# GBCZ.net
KiCad netlist of a schematic drawn in EAGLE
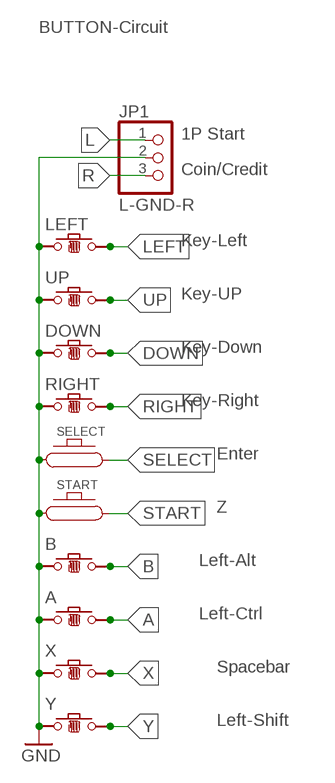
[diagram p0: schematic, sheet 1]

(export (version "E")
  (design (tool "Eeschema 10.0.6"))
  (components
    (comp (ref "A")
      (value "GBC_BTN")
      (footprint "eagle-import:GBC_BTN")
      (libsource (lib "eagle-import") (part "GBC_BTN"))
    )
    (comp (ref "B")
      (value "GBC_BTN")
      (footprint "eagle-import:GBC_BTN")
      (libsource (lib "eagle-import") (part "GBC_BTN"))
    )
    (comp (ref "DOWN")
      (value "GBC_BTN")
      (footprint "eagle-import:GBC_BTN")
      (libsource (lib "eagle-import") (part "GBC_BTN"))
    )
    (comp (ref "JP1")
      (value "L-GND-R")
      (footprint "eagle-import:1X03")
      (libsource (lib "eagle-import") (part "PINHD-1X3"))
    )
    (comp (ref "LEFT")
      (value "GBC_BTN")
      (footprint "eagle-import:GBC_BTN")
      (libsource (lib "eagle-import") (part "GBC_BTN"))
    )
    (comp (ref "RIGHT")
      (value "GBC_BTN")
      (footprint "eagle-import:GBC_BTN")
      (libsource (lib "eagle-import") (part "GBC_BTN"))
    )
    (comp (ref "SELECT")
      (value "GBC_BTN_START")
      (footprint "eagle-import:GBC_BTN_START")
      (libsource (lib "eagle-import") (part "GBC_BTN_START"))
    )
    (comp (ref "START")
      (value "GBC_BTN_START")
      (footprint "eagle-import:GBC_BTN_START")
      (libsource (lib "eagle-import") (part "GBC_BTN_START"))
    )
    (comp (ref "UP")
      (value "GBC_BTN")
      (footprint "eagle-import:GBC_BTN")
      (libsource (lib "eagle-import") (part "GBC_BTN"))
    )
    (comp (ref "X")
      (value "GBC_BTN")
      (footprint "eagle-import:GBC_BTN")
      (libsource (lib "eagle-import") (part "GBC_BTN"))
    )
    (comp (ref "Y")
      (value "GBC_BTN")
      (footprint "eagle-import:GBC_BTN")
      (libsource (lib "eagle-import") (part "GBC_BTN"))
    )
  )
  (nets
    (net (code "1") (name "A") (class "Default")
      (node (ref "A") (pin "P$2") (pinfunction "P$2_P$2") (pintype "passive"))
    )
    (net (code "2") (name "B") (class "Default")
      (node (ref "B") (pin "P$2") (pinfunction "P$2_P$2") (pintype "passive"))
    )
    (net (code "3") (name "DOWN") (class "Default")
      (node (ref "DOWN") (pin "P$2") (pinfunction "P$2_P$2") (pintype "passive"))
    )
    (net (code "4") (name "GND") (class "Default")
      (node (ref "A") (pin "P$1") (pinfunction "P$1_P$1") (pintype "passive"))
      (node (ref "B") (pin "P$1") (pinfunction "P$1_P$1") (pintype "passive"))
      (node (ref "DOWN") (pin "P$1") (pinfunction "P$1_P$1") (pintype "passive"))
      (node (ref "JP1") (pin "2") (pinfunction "2_2") (pintype "passive"))
      (node (ref "LEFT") (pin "P$1") (pinfunction "P$1_P$1") (pintype "passive"))
      (node (ref "RIGHT") (pin "P$1") (pinfunction "P$1_P$1") (pintype "passive"))
      (node (ref "SELECT") (pin "P$1") (pinfunction "P$3_P$1") (pintype "passive"))
      (node (ref "START") (pin "P$1") (pinfunction "P$3_P$1") (pintype "passive"))
      (node (ref "UP") (pin "P$1") (pinfunction "P$1_P$1") (pintype "passive"))
      (node (ref "X") (pin "P$1") (pinfunction "P$1_P$1") (pintype "passive"))
      (node (ref "Y") (pin "P$1") (pinfunction "P$1_P$1") (pintype "passive"))
    )
    (net (code "5") (name "L") (class "Default")
      (node (ref "JP1") (pin "1") (pinfunction "1_1") (pintype "passive"))
    )
    (net (code "6") (name "LEFT") (class "Default")
      (node (ref "LEFT") (pin "P$2") (pinfunction "P$2_P$2") (pintype "passive"))
    )
    (net (code "7") (name "R") (class "Default")
      (node (ref "JP1") (pin "3") (pinfunction "3_3") (pintype "passive"))
    )
    (net (code "8") (name "RIGHT") (class "Default")
      (node (ref "RIGHT") (pin "P$2") (pinfunction "P$2_P$2") (pintype "passive"))
    )
    (net (code "9") (name "SELECT") (class "Default")
      (node (ref "SELECT") (pin "P$2") (pinfunction "P$4_P$2") (pintype "passive"))
    )
    (net (code "10") (name "START") (class "Default")
      (node (ref "START") (pin "P$2") (pinfunction "P$4_P$2") (pintype "passive"))
    )
    (net (code "11") (name "UP") (class "Default")
      (node (ref "UP") (pin "P$2") (pinfunction "P$2_P$2") (pintype "passive"))
    )
    (net (code "12") (name "X") (class "Default")
      (node (ref "X") (pin "P$2") (pinfunction "P$2_P$2") (pintype "passive"))
    )
    (net (code "13") (name "Y") (class "Default")
      (node (ref "Y") (pin "P$2") (pinfunction "P$2_P$2") (pintype "passive"))
    )
  )
)
